# axiom_beta_plugin_module_1xHDMI_v0_8_r1_.net
KiCad netlist of a schematic drawn in EAGLE
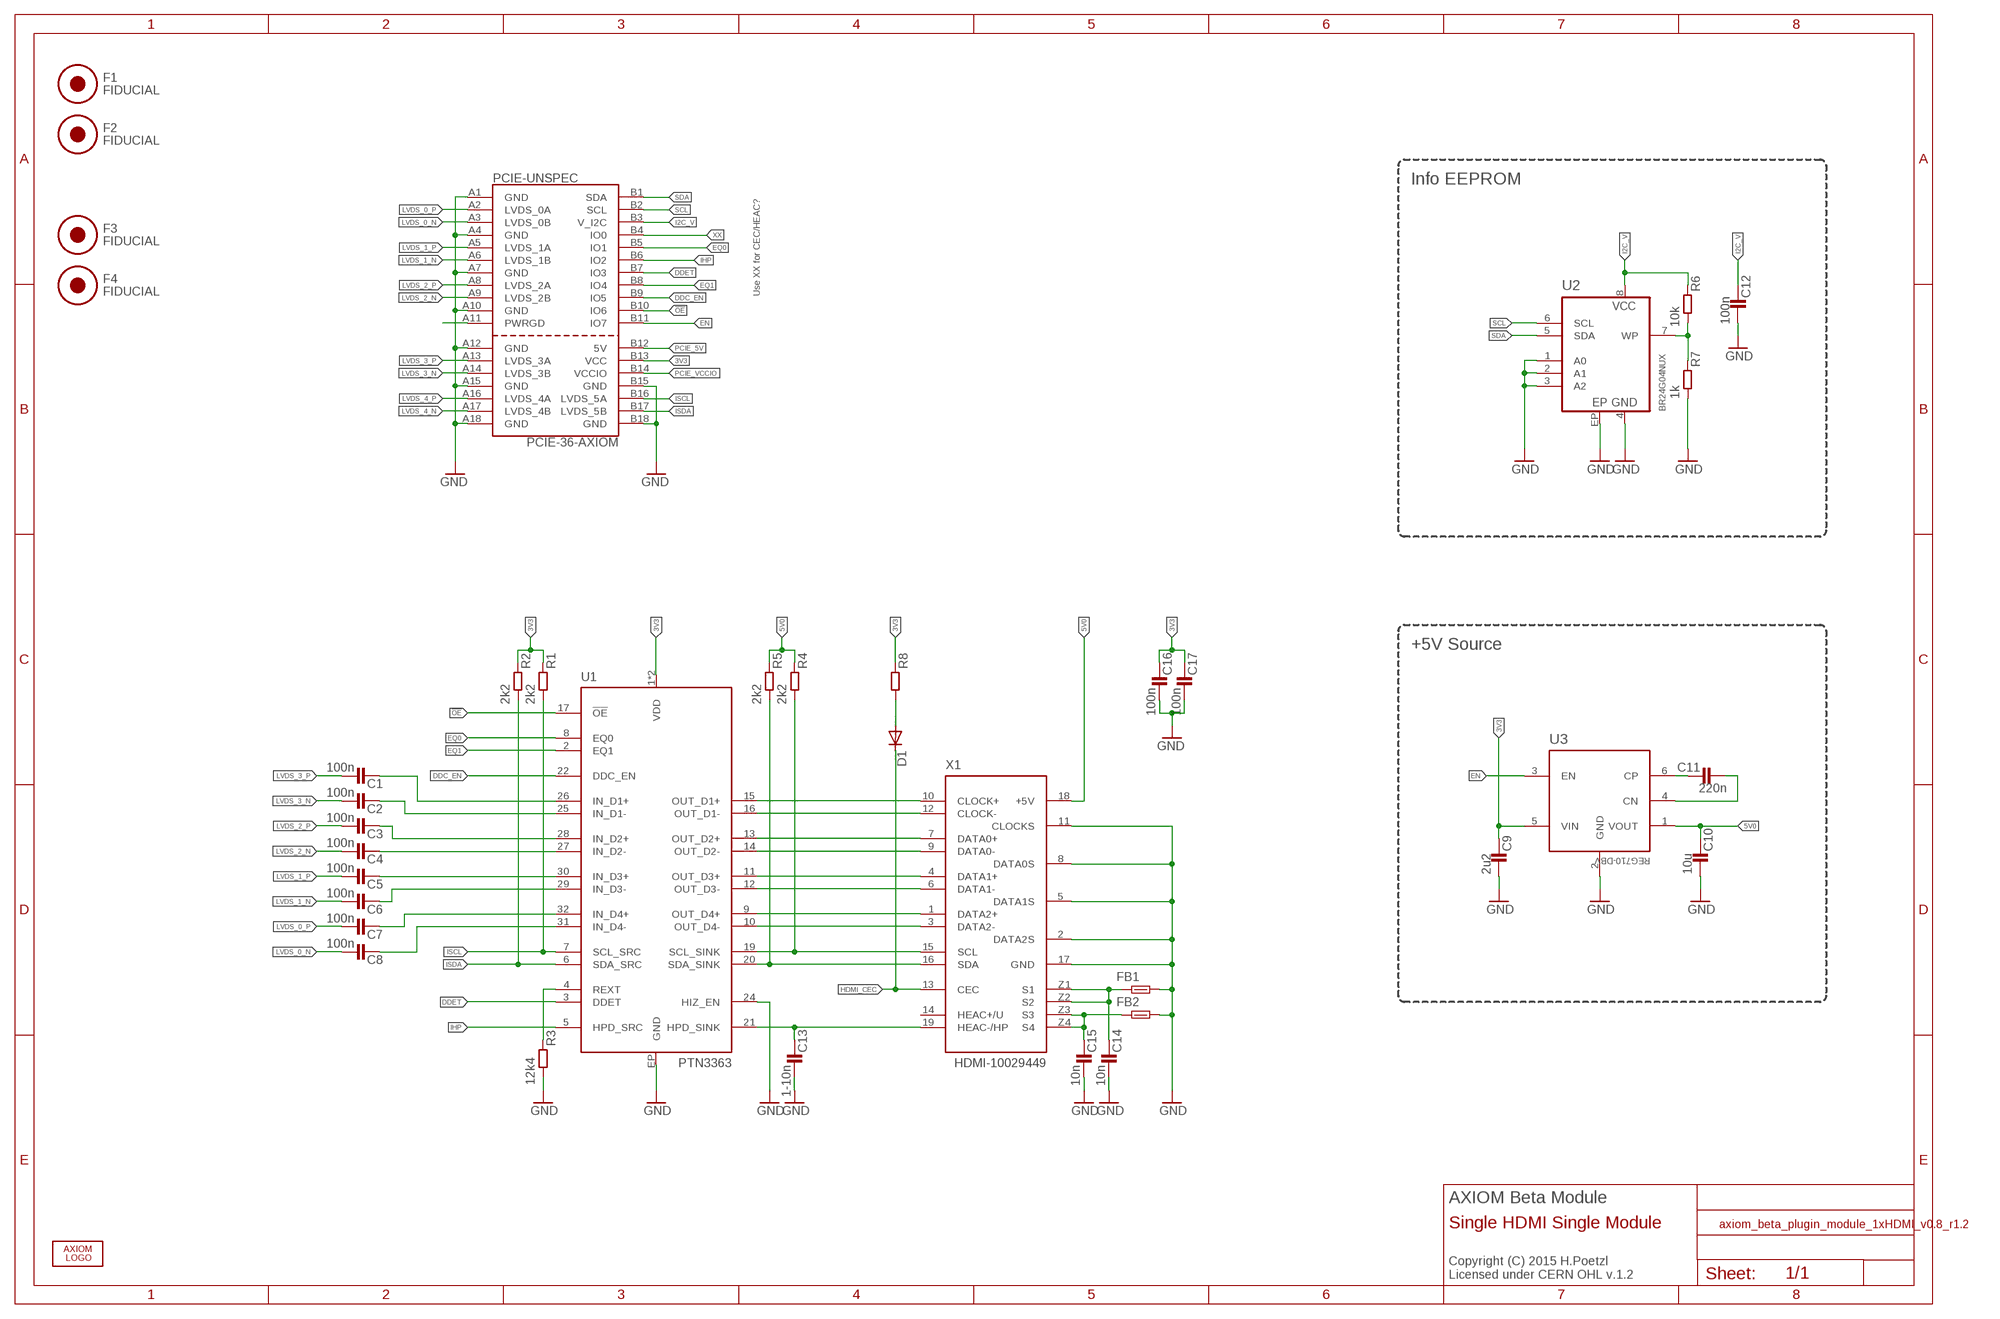
[diagram p0: schematic, sheet 1]

(export (version "E")
  (design (tool "Eeschema 10.0.6"))
  (components
    (comp (ref "C1")
      (value "100n")
      (footprint "eagle-import:0402-C")
      (libsource (lib "eagle-import") (part "C0402-C"))
    )
    (comp (ref "C2")
      (value "100n")
      (footprint "eagle-import:0402-C")
      (libsource (lib "eagle-import") (part "C0402-C"))
    )
    (comp (ref "C3")
      (value "100n")
      (footprint "eagle-import:0402-C")
      (libsource (lib "eagle-import") (part "C0402-C"))
    )
    (comp (ref "C4")
      (value "100n")
      (footprint "eagle-import:0402-C")
      (libsource (lib "eagle-import") (part "C0402-C"))
    )
    (comp (ref "C5")
      (value "100n")
      (footprint "eagle-import:0402-C")
      (libsource (lib "eagle-import") (part "C0402-C"))
    )
    (comp (ref "C6")
      (value "100n")
      (footprint "eagle-import:0402-C")
      (libsource (lib "eagle-import") (part "C0402-C"))
    )
    (comp (ref "C7")
      (value "100n")
      (footprint "eagle-import:0402-C")
      (libsource (lib "eagle-import") (part "C0402-C"))
    )
    (comp (ref "C8")
      (value "100n")
      (footprint "eagle-import:0402-C")
      (libsource (lib "eagle-import") (part "C0402-C"))
    )
    (comp (ref "C9")
      (value "2u2")
      (footprint "eagle-import:0603-B")
      (libsource (lib "eagle-import") (part "C0603-B"))
    )
    (comp (ref "C10")
      (value "10u")
      (footprint "eagle-import:0603-B")
      (libsource (lib "eagle-import") (part "C0603-B"))
    )
    (comp (ref "C11")
      (value "220n")
      (footprint "eagle-import:0603-B")
      (libsource (lib "eagle-import") (part "C0603-B"))
    )
    (comp (ref "C12")
      (value "100n")
      (footprint "eagle-import:0402-B")
      (libsource (lib "eagle-import") (part "C0402-B"))
    )
    (comp (ref "C13")
      (value "1-10n")
      (footprint "eagle-import:0402-B")
      (libsource (lib "eagle-import") (part "C0402-B"))
    )
    (comp (ref "C14")
      (value "10n")
      (footprint "eagle-import:0402-B")
      (libsource (lib "eagle-import") (part "C0402-B"))
    )
    (comp (ref "C15")
      (value "10n")
      (footprint "eagle-import:0402-B")
      (libsource (lib "eagle-import") (part "C0402-B"))
    )
    (comp (ref "C16")
      (value "100n")
      (footprint "eagle-import:0402-B")
      (libsource (lib "eagle-import") (part "C0402-B"))
    )
    (comp (ref "C17")
      (value "100n")
      (footprint "eagle-import:0402-B")
      (libsource (lib "eagle-import") (part "C0402-B"))
    )
    (comp (ref "D1")
      (value "DIODE-SOD523")
      (footprint "eagle-import:SOD523")
      (libsource (lib "eagle-import") (part "DIODE-SOD523"))
    )
    (comp (ref "F1")
      (value "FIDUCIAL")
      (footprint "eagle-import:FID_ARROW")
      (libsource (lib "eagle-import") (part "FIDUCIAL"))
    )
    (comp (ref "F2")
      (value "FIDUCIAL")
      (footprint "eagle-import:FID_ARROW")
      (libsource (lib "eagle-import") (part "FIDUCIAL"))
    )
    (comp (ref "F3")
      (value "FIDUCIAL")
      (footprint "eagle-import:FID_ARROW")
      (libsource (lib "eagle-import") (part "FIDUCIAL"))
    )
    (comp (ref "F4")
      (value "FIDUCIAL")
      (footprint "eagle-import:FID_ARROW")
      (libsource (lib "eagle-import") (part "FIDUCIAL"))
    )
    (comp (ref "FB1")
      (value "FB0603-B")
      (footprint "eagle-import:0603-B")
      (libsource (lib "eagle-import") (part "FB0603-B"))
    )
    (comp (ref "FB2")
      (value "FB0603-B")
      (footprint "eagle-import:0603-B")
      (libsource (lib "eagle-import") (part "FB0603-B"))
    )
    (comp (ref "PCIE-UNSPEC")
      (value "PCIE-36-AXIOM")
      (footprint "eagle-import:PCIE-36-AXIOM")
      (libsource (lib "eagle-import") (part "PCIE-36-AXIOM"))
    )
    (comp (ref "R1")
      (value "2k2")
      (footprint "eagle-import:0402-B")
      (libsource (lib "eagle-import") (part "R0402-B"))
    )
    (comp (ref "R2")
      (value "2k2")
      (footprint "eagle-import:0402-B")
      (libsource (lib "eagle-import") (part "R0402-B"))
    )
    (comp (ref "R3")
      (value "12k4")
      (footprint "eagle-import:0402-B")
      (libsource (lib "eagle-import") (part "R0402-B"))
    )
    (comp (ref "R4")
      (value "2k2")
      (footprint "eagle-import:0402-B")
      (libsource (lib "eagle-import") (part "R0402-B"))
    )
    (comp (ref "R5")
      (value "2k2")
      (footprint "eagle-import:0402-B")
      (libsource (lib "eagle-import") (part "R0402-B"))
    )
    (comp (ref "R6")
      (value "10k")
      (footprint "eagle-import:0402-B")
      (libsource (lib "eagle-import") (part "R0402-B"))
    )
    (comp (ref "R7")
      (value "1k")
      (footprint "eagle-import:0402-B")
      (libsource (lib "eagle-import") (part "R0402-B"))
    )
    (comp (ref "R8")
      (value "R0402-B")
      (footprint "eagle-import:0402-B")
      (libsource (lib "eagle-import") (part "R0402-B"))
    )
    (comp (ref "U$1")
      (value "AXIOM_LOGO459X70")
      (footprint "eagle-import:AXIOM_LOGO_459X70")
      (libsource (lib "eagle-import") (part "AXIOM_LOGO459X70"))
    )
    (comp (ref "U1")
      (value "PTN3363")
      (footprint "eagle-import:HVQFN32")
      (libsource (lib "eagle-import") (part "PTN3363"))
    )
    (comp (ref "U2")
      (value "BR24G04NUX")
      (footprint "eagle-import:DFN200X300X100-9N")
      (libsource (lib "eagle-import") (part "BR24G04NUX"))
    )
    (comp (ref "U3")
      (value "REG710-DBV")
      (footprint "eagle-import:DBV")
      (libsource (lib "eagle-import") (part "REG710-DBV"))
    )
    (comp (ref "X1")
      (value "HDMI-10029449")
      (footprint "eagle-import:10029449-X01XLF")
      (libsource (lib "eagle-import") (part "HDMI-10029449"))
    )
  )
  (nets
    (net (code "1") (name "/~{OE}") (class "Default")
      (node (ref "PCIE-UNSPEC") (pin "B10") (pinfunction "IO6_B10") (pintype "passive"))
      (node (ref "U1") (pin "17") (pinfunction "~{OE}_17") (pintype "bidirectional"))
    )
    (net (code "2") (name "3V3") (class "Default")
      (node (ref "C16") (pin "1") (pinfunction "1_1") (pintype "passive"))
      (node (ref "C17") (pin "1") (pinfunction "1_1") (pintype "passive"))
      (node (ref "C9") (pin "1") (pinfunction "1_1") (pintype "passive"))
      (node (ref "PCIE-UNSPEC") (pin "B13") (pinfunction "VCC_B13") (pintype "passive"))
      (node (ref "R1") (pin "1") (pinfunction "1_1") (pintype "passive"))
      (node (ref "R2") (pin "1") (pinfunction "1_1") (pintype "passive"))
      (node (ref "R8") (pin "1") (pinfunction "1_1") (pintype "passive"))
      (node (ref "U1") (pin "1") (pinfunction "VDD_1") (pintype "power_in"))
      (node (ref "U1") (pin "18") (pinfunction "VDD_18") (pintype "power_in"))
      (node (ref "U3") (pin "5") (pinfunction "VIN_5") (pintype "power_in"))
    )
    (net (code "3") (name "5V0") (class "Default")
      (node (ref "C10") (pin "1") (pinfunction "1_1") (pintype "passive"))
      (node (ref "R4") (pin "1") (pinfunction "1_1") (pintype "passive"))
      (node (ref "R5") (pin "1") (pinfunction "1_1") (pintype "passive"))
      (node (ref "U3") (pin "1") (pinfunction "VOUT_1") (pintype "output"))
      (node (ref "X1") (pin "18") (pinfunction "+5V_18") (pintype "power_in"))
    )
    (net (code "4") (name "DDC_EN") (class "Default")
      (node (ref "PCIE-UNSPEC") (pin "B9") (pinfunction "IO5_B9") (pintype "passive"))
      (node (ref "U1") (pin "22") (pinfunction "DDC_EN_22") (pintype "bidirectional"))
    )
    (net (code "5") (name "DDET") (class "Default")
      (node (ref "PCIE-UNSPEC") (pin "B7") (pinfunction "IO3_B7") (pintype "passive"))
      (node (ref "U1") (pin "3") (pinfunction "DDET_3") (pintype "bidirectional"))
    )
    (net (code "6") (name "EN") (class "Default")
      (node (ref "PCIE-UNSPEC") (pin "B11") (pinfunction "IO7_B11") (pintype "passive"))
      (node (ref "U3") (pin "3") (pinfunction "EN_3") (pintype "input"))
    )
    (net (code "7") (name "EQ0") (class "Default")
      (node (ref "PCIE-UNSPEC") (pin "B5") (pinfunction "IO1_B5") (pintype "passive"))
      (node (ref "U1") (pin "8") (pinfunction "EQ0_8") (pintype "bidirectional"))
    )
    (net (code "8") (name "EQ1") (class "Default")
      (node (ref "PCIE-UNSPEC") (pin "B8") (pinfunction "IO4_B8") (pintype "passive"))
      (node (ref "U1") (pin "2") (pinfunction "EQ1_2") (pintype "bidirectional"))
    )
    (net (code "9") (name "GND") (class "Default")
      (node (ref "C10") (pin "2") (pinfunction "2_2") (pintype "passive"))
      (node (ref "C12") (pin "2") (pinfunction "2_2") (pintype "passive"))
      (node (ref "C13") (pin "2") (pinfunction "2_2") (pintype "passive"))
      (node (ref "C14") (pin "2") (pinfunction "2_2") (pintype "passive"))
      (node (ref "C15") (pin "2") (pinfunction "2_2") (pintype "passive"))
      (node (ref "C16") (pin "2") (pinfunction "2_2") (pintype "passive"))
      (node (ref "C17") (pin "2") (pinfunction "2_2") (pintype "passive"))
      (node (ref "C9") (pin "2") (pinfunction "2_2") (pintype "passive"))
      (node (ref "FB1") (pin "2") (pinfunction "2_2") (pintype "passive"))
      (node (ref "FB2") (pin "2") (pinfunction "2_2") (pintype "passive"))
      (node (ref "PCIE-UNSPEC") (pin "A1") (pinfunction "GND_A1") (pintype "passive"))
      (node (ref "PCIE-UNSPEC") (pin "A10") (pinfunction "GND_A10") (pintype "passive"))
      (node (ref "PCIE-UNSPEC") (pin "A12") (pinfunction "GND_A12") (pintype "passive"))
      (node (ref "PCIE-UNSPEC") (pin "A15") (pinfunction "GND_A15") (pintype "passive"))
      (node (ref "PCIE-UNSPEC") (pin "A18") (pinfunction "GND_A18") (pintype "passive"))
      (node (ref "PCIE-UNSPEC") (pin "A4") (pinfunction "GND_A4") (pintype "passive"))
      (node (ref "PCIE-UNSPEC") (pin "A7") (pinfunction "GND_A7") (pintype "passive"))
      (node (ref "PCIE-UNSPEC") (pin "B15") (pinfunction "GND_B15") (pintype "passive"))
      (node (ref "PCIE-UNSPEC") (pin "B18") (pinfunction "GND_B18") (pintype "passive"))
      (node (ref "R3") (pin "2") (pinfunction "2_2") (pintype "passive"))
      (node (ref "R7") (pin "2") (pinfunction "2_2") (pintype "passive"))
      (node (ref "U1") (pin "24") (pinfunction "HIZ_EN_24") (pintype "bidirectional"))
      (node (ref "U1") (pin "EP") (pinfunction "GND_EP") (pintype "bidirectional"))
      (node (ref "U2") (pin "1") (pinfunction "A0_1") (pintype "input"))
      (node (ref "U2") (pin "2") (pinfunction "A1_2") (pintype "input"))
      (node (ref "U2") (pin "3") (pinfunction "A2_3") (pintype "input"))
      (node (ref "U2") (pin "4") (pinfunction "GND_4") (pintype "passive"))
      (node (ref "U2") (pin "EP") (pinfunction "EP_EP") (pintype "passive"))
      (node (ref "U3") (pin "2") (pinfunction "GND_2") (pintype "passive"))
      (node (ref "X1") (pin "11") (pinfunction "CLOCKS_11") (pintype "power_in"))
      (node (ref "X1") (pin "17") (pinfunction "GND_17") (pintype "bidirectional"))
      (node (ref "X1") (pin "2") (pinfunction "DATA2S_2") (pintype "power_in"))
      (node (ref "X1") (pin "5") (pinfunction "DATA1S_5") (pintype "power_in"))
      (node (ref "X1") (pin "8") (pinfunction "DATA0S_8") (pintype "power_in"))
    )
    (net (code "10") (name "HDMI_CEC") (class "Default")
      (node (ref "D1") (pin "C") (pinfunction "C_C") (pintype "passive"))
      (node (ref "X1") (pin "13") (pinfunction "CEC_13") (pintype "bidirectional"))
    )
    (net (code "11") (name "I2C_V") (class "Default")
      (node (ref "C12") (pin "1") (pinfunction "1_1") (pintype "passive"))
      (node (ref "PCIE-UNSPEC") (pin "B3") (pinfunction "V_I2C_B3") (pintype "passive"))
      (node (ref "R6") (pin "1") (pinfunction "1_1") (pintype "passive"))
      (node (ref "U2") (pin "8") (pinfunction "VCC_8") (pintype "power_in"))
    )
    (net (code "12") (name "IHP") (class "Default")
      (node (ref "PCIE-UNSPEC") (pin "B6") (pinfunction "IO2_B6") (pintype "passive"))
      (node (ref "U1") (pin "5") (pinfunction "HPD_SRC_5") (pintype "bidirectional"))
    )
    (net (code "13") (name "ISCL") (class "Default")
      (node (ref "PCIE-UNSPEC") (pin "B16") (pinfunction "LVDS_5A_B16") (pintype "passive"))
      (node (ref "R1") (pin "2") (pinfunction "2_2") (pintype "passive"))
      (node (ref "U1") (pin "7") (pinfunction "SCL_SRC_7") (pintype "bidirectional"))
    )
    (net (code "14") (name "ISDA") (class "Default")
      (node (ref "PCIE-UNSPEC") (pin "B17") (pinfunction "LVDS_5B_B17") (pintype "passive"))
      (node (ref "R2") (pin "2") (pinfunction "2_2") (pintype "passive"))
      (node (ref "U1") (pin "6") (pinfunction "SDA_SRC_6") (pintype "bidirectional"))
    )
    (net (code "15") (name "LVDS_0_N") (class "Default")
      (node (ref "C8") (pin "2") (pinfunction "2_2") (pintype "passive"))
      (node (ref "PCIE-UNSPEC") (pin "A3") (pinfunction "LVDS_0B_A3") (pintype "passive"))
    )
    (net (code "16") (name "LVDS_0_P") (class "Default")
      (node (ref "C7") (pin "2") (pinfunction "2_2") (pintype "passive"))
      (node (ref "PCIE-UNSPEC") (pin "A2") (pinfunction "LVDS_0A_A2") (pintype "passive"))
    )
    (net (code "17") (name "LVDS_1_N") (class "Default")
      (node (ref "C6") (pin "2") (pinfunction "2_2") (pintype "passive"))
      (node (ref "PCIE-UNSPEC") (pin "A6") (pinfunction "LVDS_1B_A6") (pintype "passive"))
    )
    (net (code "18") (name "LVDS_1_P") (class "Default")
      (node (ref "C5") (pin "2") (pinfunction "2_2") (pintype "passive"))
      (node (ref "PCIE-UNSPEC") (pin "A5") (pinfunction "LVDS_1A_A5") (pintype "passive"))
    )
    (net (code "19") (name "LVDS_2_N") (class "Default")
      (node (ref "C4") (pin "2") (pinfunction "2_2") (pintype "passive"))
      (node (ref "PCIE-UNSPEC") (pin "A9") (pinfunction "LVDS_2B_A9") (pintype "passive"))
    )
    (net (code "20") (name "LVDS_2_P") (class "Default")
      (node (ref "C3") (pin "2") (pinfunction "2_2") (pintype "passive"))
      (node (ref "PCIE-UNSPEC") (pin "A8") (pinfunction "LVDS_2A_A8") (pintype "passive"))
    )
    (net (code "21") (name "LVDS_3_N") (class "Default")
      (node (ref "C2") (pin "2") (pinfunction "2_2") (pintype "passive"))
      (node (ref "PCIE-UNSPEC") (pin "A14") (pinfunction "LVDS_3B_A14") (pintype "passive"))
    )
    (net (code "22") (name "LVDS_3_P") (class "Default")
      (node (ref "C1") (pin "2") (pinfunction "2_2") (pintype "passive"))
      (node (ref "PCIE-UNSPEC") (pin "A13") (pinfunction "LVDS_3A_A13") (pintype "passive"))
    )
    (net (code "23") (name "LVDS_4_N") (class "Default")
      (node (ref "PCIE-UNSPEC") (pin "A17") (pinfunction "LVDS_4B_A17") (pintype "passive"))
    )
    (net (code "24") (name "LVDS_4_P") (class "Default")
      (node (ref "PCIE-UNSPEC") (pin "A16") (pinfunction "LVDS_4A_A16") (pintype "passive"))
    )
    (net (code "25") (name "Net-(D1-PadA)") (class "Default")
      (node (ref "D1") (pin "A") (pinfunction "A_A") (pintype "passive"))
      (node (ref "R8") (pin "2") (pinfunction "2_2") (pintype "passive"))
    )
    (net (code "26") (name "Net-(U1-HPD_SINK)") (class "Default")
      (node (ref "C13") (pin "1") (pinfunction "1_1") (pintype "passive"))
      (node (ref "U1") (pin "21") (pinfunction "HPD_SINK_21") (pintype "bidirectional"))
      (node (ref "X1") (pin "19") (pinfunction "HEAC-/HP_19") (pintype "bidirectional"))
    )
    (net (code "27") (name "Net-(U1-IN_D1+)") (class "Default")
      (node (ref "C1") (pin "1") (pinfunction "1_1") (pintype "passive"))
      (node (ref "U1") (pin "26") (pinfunction "IN_D1+_26") (pintype "bidirectional"))
    )
    (net (code "28") (name "Net-(U1-IN_D1-)") (class "Default")
      (node (ref "C2") (pin "1") (pinfunction "1_1") (pintype "passive"))
      (node (ref "U1") (pin "25") (pinfunction "IN_D1-_25") (pintype "bidirectional"))
    )
    (net (code "29") (name "Net-(U1-IN_D2+)") (class "Default")
      (node (ref "C3") (pin "1") (pinfunction "1_1") (pintype "passive"))
      (node (ref "U1") (pin "28") (pinfunction "IN_D2+_28") (pintype "bidirectional"))
    )
    (net (code "30") (name "Net-(U1-IN_D2-)") (class "Default")
      (node (ref "C4") (pin "1") (pinfunction "1_1") (pintype "passive"))
      (node (ref "U1") (pin "27") (pinfunction "IN_D2-_27") (pintype "bidirectional"))
    )
    (net (code "31") (name "Net-(U1-IN_D3+)") (class "Default")
      (node (ref "C5") (pin "1") (pinfunction "1_1") (pintype "passive"))
      (node (ref "U1") (pin "30") (pinfunction "IN_D3+_30") (pintype "bidirectional"))
    )
    (net (code "32") (name "Net-(U1-IN_D3-)") (class "Default")
      (node (ref "C6") (pin "1") (pinfunction "1_1") (pintype "passive"))
      (node (ref "U1") (pin "29") (pinfunction "IN_D3-_29") (pintype "bidirectional"))
    )
    (net (code "33") (name "Net-(U1-IN_D4+)") (class "Default")
      (node (ref "C7") (pin "1") (pinfunction "1_1") (pintype "passive"))
      (node (ref "U1") (pin "32") (pinfunction "IN_D4+_32") (pintype "bidirectional"))
    )
    (net (code "34") (name "Net-(U1-IN_D4-)") (class "Default")
      (node (ref "C8") (pin "1") (pinfunction "1_1") (pintype "passive"))
      (node (ref "U1") (pin "31") (pinfunction "IN_D4-_31") (pintype "bidirectional"))
    )
    (net (code "35") (name "Net-(U1-OUT_D1+)") (class "Default")
      (node (ref "U1") (pin "15") (pinfunction "OUT_D1+_15") (pintype "bidirectional"))
      (node (ref "X1") (pin "10") (pinfunction "CLOCK+_10") (pintype "bidirectional"))
    )
    (net (code "36") (name "Net-(U1-OUT_D1-)") (class "Default")
      (node (ref "U1") (pin "16") (pinfunction "OUT_D1-_16") (pintype "bidirectional"))
      (node (ref "X1") (pin "12") (pinfunction "CLOCK-_12") (pintype "bidirectional"))
    )
    (net (code "37") (name "Net-(U1-OUT_D2+)") (class "Default")
      (node (ref "U1") (pin "13") (pinfunction "OUT_D2+_13") (pintype "bidirectional"))
      (node (ref "X1") (pin "7") (pinfunction "DATA0+_7") (pintype "bidirectional"))
    )
    (net (code "38") (name "Net-(U1-OUT_D2-)") (class "Default")
      (node (ref "U1") (pin "14") (pinfunction "OUT_D2-_14") (pintype "bidirectional"))
      (node (ref "X1") (pin "9") (pinfunction "DATA0-_9") (pintype "bidirectional"))
    )
    (net (code "39") (name "Net-(U1-OUT_D3+)") (class "Default")
      (node (ref "U1") (pin "11") (pinfunction "OUT_D3+_11") (pintype "bidirectional"))
      (node (ref "X1") (pin "4") (pinfunction "DATA1+_4") (pintype "bidirectional"))
    )
    (net (code "40") (name "Net-(U1-OUT_D3-)") (class "Default")
      (node (ref "U1") (pin "12") (pinfunction "OUT_D3-_12") (pintype "bidirectional"))
      (node (ref "X1") (pin "6") (pinfunction "DATA1-_6") (pintype "bidirectional"))
    )
    (net (code "41") (name "Net-(U1-OUT_D4+)") (class "Default")
      (node (ref "U1") (pin "9") (pinfunction "OUT_D4+_9") (pintype "bidirectional"))
      (node (ref "X1") (pin "1") (pinfunction "DATA2+_1") (pintype "bidirectional"))
    )
    (net (code "42") (name "Net-(U1-OUT_D4-)") (class "Default")
      (node (ref "U1") (pin "10") (pinfunction "OUT_D4-_10") (pintype "bidirectional"))
      (node (ref "X1") (pin "3") (pinfunction "DATA2-_3") (pintype "bidirectional"))
    )
    (net (code "43") (name "Net-(U1-REXT)") (class "Default")
      (node (ref "R3") (pin "1") (pinfunction "1_1") (pintype "passive"))
      (node (ref "U1") (pin "4") (pinfunction "REXT_4") (pintype "bidirectional"))
    )
    (net (code "44") (name "Net-(U1-SCL_SINK)") (class "Default")
      (node (ref "R4") (pin "2") (pinfunction "2_2") (pintype "passive"))
      (node (ref "U1") (pin "19") (pinfunction "SCL_SINK_19") (pintype "bidirectional"))
      (node (ref "X1") (pin "15") (pinfunction "SCL_15") (pintype "bidirectional"))
    )
    (net (code "45") (name "Net-(U1-SDA_SINK)") (class "Default")
      (node (ref "R5") (pin "2") (pinfunction "2_2") (pintype "passive"))
      (node (ref "U1") (pin "20") (pinfunction "SDA_SINK_20") (pintype "bidirectional"))
      (node (ref "X1") (pin "16") (pinfunction "SDA_16") (pintype "bidirectional"))
    )
    (net (code "46") (name "Net-(U2-WP)") (class "Default")
      (node (ref "R6") (pin "2") (pinfunction "2_2") (pintype "passive"))
      (node (ref "R7") (pin "1") (pinfunction "1_1") (pintype "passive"))
      (node (ref "U2") (pin "7") (pinfunction "WP_7") (pintype "input"))
    )
    (net (code "47") (name "Net-(U3-CN)") (class "Default")
      (node (ref "C11") (pin "2") (pinfunction "2_2") (pintype "passive"))
      (node (ref "U3") (pin "4") (pinfunction "CN_4") (pintype "power_in"))
    )
    (net (code "48") (name "Net-(U3-CP)") (class "Default")
      (node (ref "C11") (pin "1") (pinfunction "1_1") (pintype "passive"))
      (node (ref "U3") (pin "6") (pinfunction "CP_6") (pintype "output"))
    )
    (net (code "49") (name "Net-(X1-S1)") (class "Default")
      (node (ref "C14") (pin "1") (pinfunction "1_1") (pintype "passive"))
      (node (ref "FB1") (pin "1") (pinfunction "1_1") (pintype "passive"))
      (node (ref "X1") (pin "Z1") (pinfunction "S1_Z1") (pintype "power_in"))
      (node (ref "X1") (pin "Z2") (pinfunction "S2_Z2") (pintype "power_in"))
    )
    (net (code "50") (name "Net-(X1-S3)") (class "Default")
      (node (ref "C15") (pin "1") (pinfunction "1_1") (pintype "passive"))
      (node (ref "FB2") (pin "1") (pinfunction "1_1") (pintype "passive"))
      (node (ref "X1") (pin "Z3") (pinfunction "S3_Z3") (pintype "power_in"))
      (node (ref "X1") (pin "Z4") (pinfunction "S4_Z4") (pintype "power_in"))
    )
    (net (code "51") (name "PCIE_5V") (class "Default")
      (node (ref "PCIE-UNSPEC") (pin "B12") (pinfunction "5V_B12") (pintype "passive"))
    )
    (net (code "52") (name "PCIE_VCCIO") (class "Default")
      (node (ref "PCIE-UNSPEC") (pin "B14") (pinfunction "VCCIO_B14") (pintype "passive"))
    )
    (net (code "53") (name "SCL") (class "Default")
      (node (ref "PCIE-UNSPEC") (pin "B2") (pinfunction "SCL_B2") (pintype "passive"))
      (node (ref "U2") (pin "6") (pinfunction "SCL_6") (pintype "input"))
    )
    (net (code "54") (name "SDA") (class "Default")
      (node (ref "PCIE-UNSPEC") (pin "B1") (pinfunction "SDA_B1") (pintype "passive"))
      (node (ref "U2") (pin "5") (pinfunction "SDA_5") (pintype "bidirectional"))
    )
    (net (code "55") (name "XX") (class "Default")
      (node (ref "PCIE-UNSPEC") (pin "B4") (pinfunction "IO0_B4") (pintype "passive"))
    )
    (net (code "56") (name "unconnected-(PCIE-UNSPEC-PWRGD-PadA11)") (class "Default")
      (node (ref "PCIE-UNSPEC") (pin "A11") (pinfunction "PWRGD_A11") (pintype "passive"))
    )
    (net (code "57") (name "unconnected-(X1-HEAC+{slash}U-Pad14)") (class "Default")
      (node (ref "X1") (pin "14") (pinfunction "HEAC+/U_14") (pintype "bidirectional"))
    )
  )
)
